# EtherCAT_Sheet.net
KiCad netlist of a schematic drawn in Altium Designer
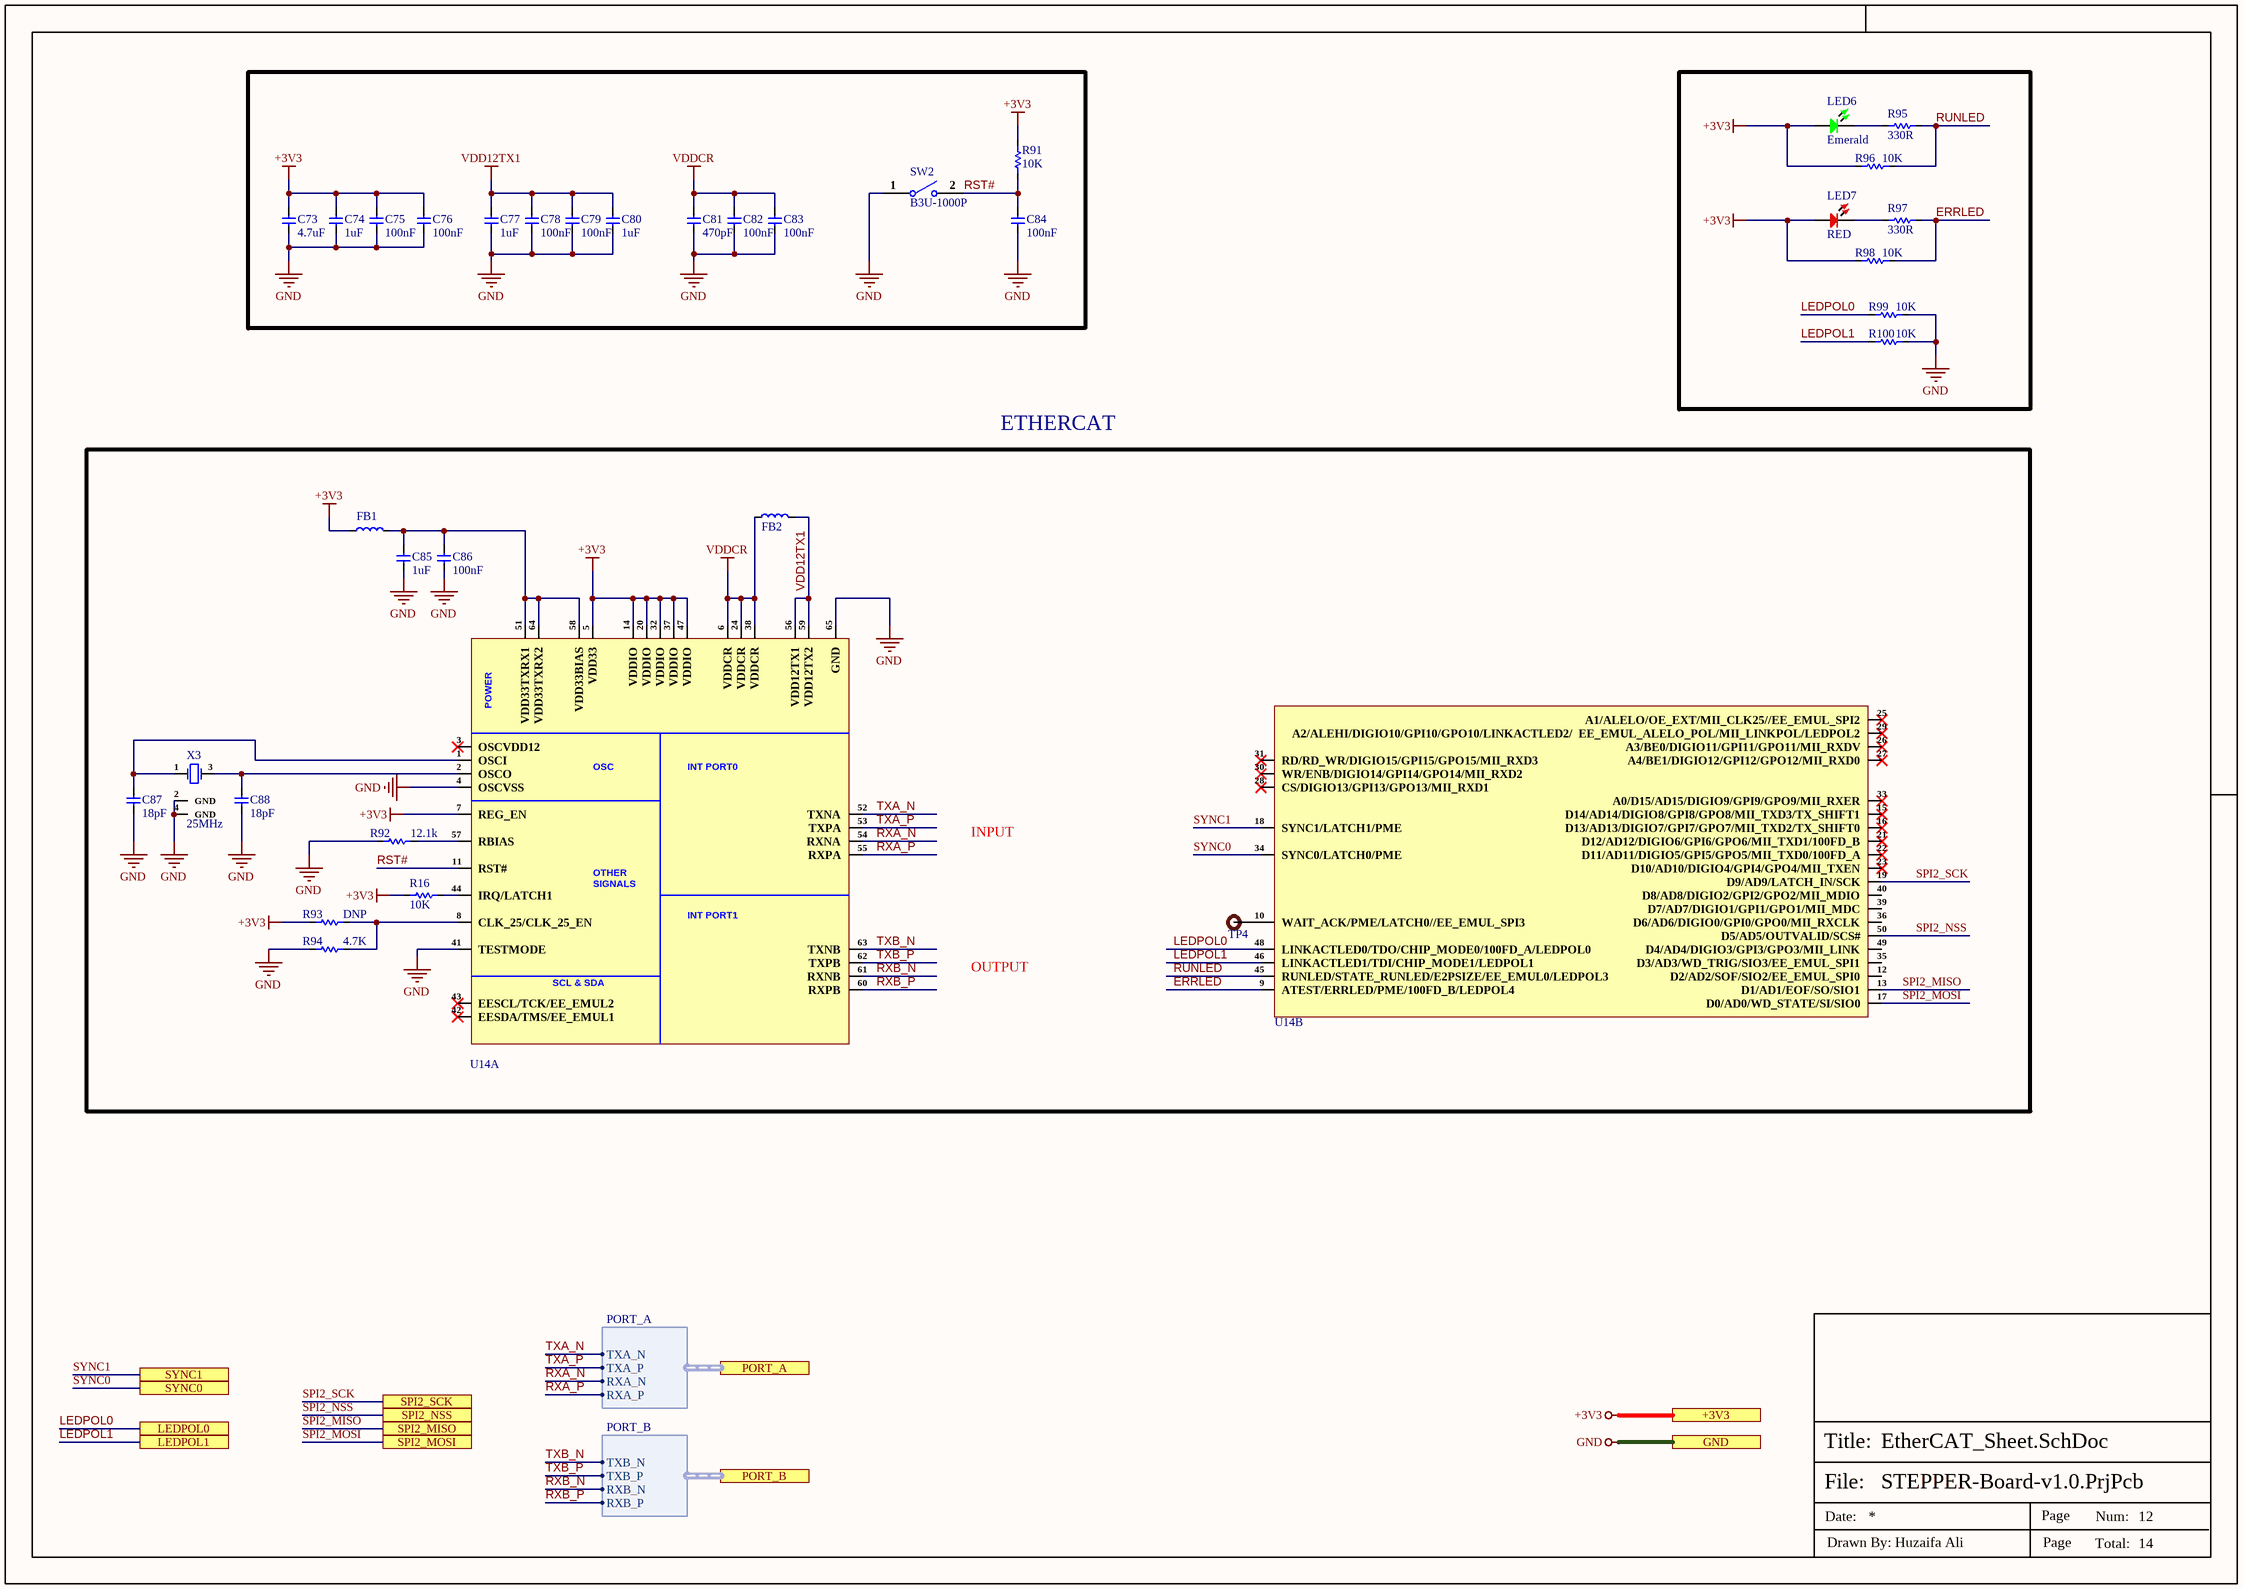
[diagram p0: EtherCAT_Sheet.SchDoc]

(export (version "E")
  (design (tool "Eeschema 10.0.6"))
  (components
    (comp (ref "C73")
      (value "4.7uF")
      (footprint "Cap-0402")
      (description "CAP CER 4.7UF 10V X5R 0402")
      (fields
        (field (name "MANUFACTURER") "Yageo")
        (field (name "MANUFACTURER PART NUMBER") "CC0402KRX5R6BB475")
      )
      (libsource (lib "eSpark Libraries") (part "CC0402KRX5R6BB475"))
    )
    (comp (ref "C74")
      (value "1uF")
      (footprint "Cap-0402")
      (description "CAP CER 1UF 10V X5R 0402")
      (fields
        (field (name "MANUFACTURER") "Yageo")
        (field (name "MANUFACTURER PART NUMBER") "CC0402KRX5R6BB105")
      )
      (libsource (lib "eSpark Libraries") (part "CC0402KRX5R6BB105"))
    )
    (comp (ref "C75")
      (value "100nF")
      (footprint "cap-0402")
      (description "CAP CER 0.1UF 50V X7R 0402")
      (fields
        (field (name "MANUFACTURER") "TDK")
        (field (name "MANUFACTURER PART NUMBER") "C1005X7R1H104KT000F")
      )
      (libsource (lib "eSpark Libraries") (part "C1005X7R1H104KT000F"))
    )
    (comp (ref "C76")
      (value "100nF")
      (footprint "cap-0402")
      (description "CAP CER 0.1UF 50V X7R 0402")
      (fields
        (field (name "MANUFACTURER") "TDK")
        (field (name "MANUFACTURER PART NUMBER") "C1005X7R1H104KT000F")
      )
      (libsource (lib "eSpark Libraries") (part "C1005X7R1H104KT000F"))
    )
    (comp (ref "C77")
      (value "1uF")
      (footprint "Cap-0402")
      (description "CAP CER 1UF 10V X5R 0402")
      (fields
        (field (name "MANUFACTURER") "Yageo")
        (field (name "MANUFACTURER PART NUMBER") "CC0402KRX5R6BB105")
      )
      (libsource (lib "eSpark Libraries") (part "CC0402KRX5R6BB105"))
    )
    (comp (ref "C78")
      (value "100nF")
      (footprint "cap-0402")
      (description "CAP CER 0.1UF 50V X7R 0402")
      (fields
        (field (name "MANUFACTURER") "TDK")
        (field (name "MANUFACTURER PART NUMBER") "C1005X7R1H104KT000F")
      )
      (libsource (lib "eSpark Libraries") (part "C1005X7R1H104KT000F"))
    )
    (comp (ref "C79")
      (value "100nF")
      (footprint "cap-0402")
      (description "CAP CER 0.1UF 50V X7R 0402")
      (fields
        (field (name "MANUFACTURER") "TDK")
        (field (name "MANUFACTURER PART NUMBER") "C1005X7R1H104KT000F")
      )
      (libsource (lib "eSpark Libraries") (part "C1005X7R1H104KT000F"))
    )
    (comp (ref "C80")
      (value "1uF")
      (footprint "Cap-0402")
      (description "CAP CER 1UF 10V X5R 0402")
      (fields
        (field (name "MANUFACTURER") "Yageo")
        (field (name "MANUFACTURER PART NUMBER") "CC0402KRX5R6BB105")
      )
      (libsource (lib "eSpark Libraries") (part "CC0402KRX5R6BB105"))
    )
    (comp (ref "C81")
      (value "470pF")
      (footprint "Cap-0603")
      (description "CAP CER 470PF 50V X7R 0603")
      (fields
        (field (name "MANUFACTURER") "Walsin Technologies")
        (field (name "MANUFACTURER PART NUMBER") "0603B471K500CT")
      )
      (libsource (lib "eSpark Libraries") (part "0603B471K500CT"))
    )
    (comp (ref "C82")
      (value "100nF")
      (footprint "cap-0402")
      (description "CAP CER 0.1UF 50V X7R 0402")
      (fields
        (field (name "MANUFACTURER") "TDK")
        (field (name "MANUFACTURER PART NUMBER") "C1005X7R1H104KT000F")
      )
      (libsource (lib "eSpark Libraries") (part "C1005X7R1H104KT000F"))
    )
    (comp (ref "C83")
      (value "100nF")
      (footprint "cap-0402")
      (description "CAP CER 0.1UF 50V X7R 0402")
      (fields
        (field (name "MANUFACTURER") "TDK")
        (field (name "MANUFACTURER PART NUMBER") "C1005X7R1H104KT000F")
      )
      (libsource (lib "eSpark Libraries") (part "C1005X7R1H104KT000F"))
    )
    (comp (ref "C84")
      (value "100nF")
      (footprint "cap-0402")
      (description "CAP CER 0.1UF 50V X7R 0402")
      (fields
        (field (name "MANUFACTURER") "TDK")
        (field (name "MANUFACTURER PART NUMBER") "C1005X7R1H104KT000F")
      )
      (libsource (lib "eSpark Libraries") (part "C1005X7R1H104KT000F"))
    )
    (comp (ref "C85")
      (value "1uF")
      (footprint "Cap-0402")
      (description "CAP CER 1UF 10V X5R 0402")
      (fields
        (field (name "MANUFACTURER") "Yageo")
        (field (name "MANUFACTURER PART NUMBER") "CC0402KRX5R6BB105")
      )
      (libsource (lib "eSpark Libraries") (part "CC0402KRX5R6BB105"))
    )
    (comp (ref "C86")
      (value "100nF")
      (footprint "cap-0402")
      (description "CAP CER 0.1UF 50V X7R 0402")
      (fields
        (field (name "MANUFACTURER") "TDK")
        (field (name "MANUFACTURER PART NUMBER") "C1005X7R1H104KT000F")
      )
      (libsource (lib "eSpark Libraries") (part "C1005X7R1H104KT000F"))
    )
    (comp (ref "C87")
      (value "18pF")
      (footprint "Cap-0402")
      (description "CAP CER 18PF 50V C0G/NP0 0402")
      (fields
        (field (name "MANUFACTURER") "Murata")
        (field (name "MANUFACTURER PART NUMBER") "GCM1555C1H180GA16D")
      )
      (libsource (lib "eSpark Libraries") (part "GCM1555C1H180GA16D"))
    )
    (comp (ref "C88")
      (value "18pF")
      (footprint "Cap-0402")
      (description "CAP CER 18PF 50V C0G/NP0 0402")
      (fields
        (field (name "MANUFACTURER") "Murata")
        (field (name "MANUFACTURER PART NUMBER") "GCM1555C1H180GA16D")
      )
      (libsource (lib "eSpark Libraries") (part "GCM1555C1H180GA16D"))
    )
    (comp (ref "FB1")
      (value "BLM15PG100SN1D")
      (footprint "IND-0402")
      (description "FERRITE BEAD 10 OHM 0402 1LN")
      (fields (field (name "MANUFACTURER") "Murata") (field (name "TOLERANCE") "25%"))
      (libsource (lib "eSpark Libraries") (part "BLM15PG100SN1D"))
    )
    (comp (ref "FB2")
      (value "BLM15PG100SN1D")
      (footprint "IND-0402")
      (description "FERRITE BEAD 10 OHM 0402 1LN")
      (fields (field (name "MANUFACTURER") "Murata") (field (name "TOLERANCE") "25%"))
      (libsource (lib "eSpark Libraries") (part "BLM15PG100SN1D"))
    )
    (comp (ref "LED6")
      (value "Emerald")
      (footprint "LED-0603")
      (description "Emerald 0603 Light Emitting Diodes (LED) ROHS")
      (fields
        (field (name "MANUFACTURER") "Foshan NationStar Optoelectronics")
        (field (name "MANUFACTURER PART NUMBER") "NCD0603G2")
      )
      (libsource (lib "eSpark Libraries") (part "NCD0603G2"))
    )
    (comp (ref "LED7")
      (value "RED")
      (footprint "LED-0603")
      (description "RED LED 0603 Light Emitting Diodes")
      (fields
        (field (name "MANUFACTURER") "Foshan NationStar Optoelectronics")
        (field (name "MANUFACTURER PART NUMBER") "NCD0603R3")
      )
      (libsource (lib "eSpark Libraries") (part "NCD0603R3"))
    )
    (comp (ref "R16")
      (value "10K")
      (footprint "Res-0402")
      (description "RES 10K OHM 1% 1/16W 0402")
      (fields
        (field (name "MANUFACTURER") "Yageo")
        (field (name "MANUFACTURER PART NUMBER") "RC0402FR-0710KL")
      )
      (libsource (lib "eSpark Libraries") (part "RC0402FR-0710KL"))
    )
    (comp (ref "R91")
      (value "10K")
      (footprint "Res-0402")
      (description "RES 10K OHM 1% 1/16W 0402")
      (fields
        (field (name "MANUFACTURER") "Yageo")
        (field (name "MANUFACTURER PART NUMBER") "RC0402FR-0710KL")
      )
      (libsource (lib "eSpark Libraries") (part "RC0402FR-0710KL"))
    )
    (comp (ref "R92")
      (value "12.1k")
      (footprint "Res-0402")
      (description "RES SMD 12.1KOHM 0.1% 1/16W 0402")
      (fields
        (field (name "MANUFACTURER") "Yageo")
        (field (name "MANUFACTURER PART NUMBER") "RT0402BRD0712K1L")
      )
      (libsource (lib "eSpark Libraries") (part "RT0402BRD0712K1L"))
    )
    (comp (ref "R93")
      (value "DNP")
      (footprint "Res-0402")
      (description "RES 4.7K OHM 1% 1/16W 0402")
      (fields
        (field (name "MANUFACTURER") "Yageo")
        (field (name "MANUFACTURER PART NUMBER") "RC0402FR-074K7L")
      )
      (libsource (lib "eSpark Libraries") (part "RC0402FR-074K7L"))
    )
    (comp (ref "R94")
      (value "4.7K")
      (footprint "Res-0402")
      (description "RES 4.7K OHM 1% 1/16W 0402")
      (fields
        (field (name "MANUFACTURER") "Yageo")
        (field (name "MANUFACTURER PART NUMBER") "RC0402FR-074K7L")
      )
      (libsource (lib "eSpark Libraries") (part "RC0402FR-074K7L"))
    )
    (comp (ref "R95")
      (value "330R")
      (footprint "Res-0603")
      (description "RES  SMD 330R 100 mW 0603")
      (fields
        (field (name "MANUFACTURER") "Yageo")
        (field (name "MANUFACTURER PART NUMBER") "RC0603JR-07330RL")
      )
      (libsource (lib "eSpark Libraries") (part "RC0603JR-07330RL"))
    )
    (comp (ref "R96")
      (value "10K")
      (footprint "Res-0402")
      (description "RES 10K OHM 1% 1/16W 0402")
      (fields
        (field (name "MANUFACTURER") "Yageo")
        (field (name "MANUFACTURER PART NUMBER") "RC0402FR-0710KL")
      )
      (libsource (lib "eSpark Libraries") (part "RC0402FR-0710KL"))
    )
    (comp (ref "R97")
      (value "330R")
      (footprint "Res-0603")
      (description "RES  SMD 330R 100 mW 0603")
      (fields
        (field (name "MANUFACTURER") "Yageo")
        (field (name "MANUFACTURER PART NUMBER") "RC0603JR-07330RL")
      )
      (libsource (lib "eSpark Libraries") (part "RC0603JR-07330RL"))
    )
    (comp (ref "R98")
      (value "10K")
      (footprint "Res-0402")
      (description "RES 10K OHM 1% 1/16W 0402")
      (fields
        (field (name "MANUFACTURER") "Yageo")
        (field (name "MANUFACTURER PART NUMBER") "RC0402FR-0710KL")
      )
      (libsource (lib "eSpark Libraries") (part "RC0402FR-0710KL"))
    )
    (comp (ref "R99")
      (value "10K")
      (footprint "Res-0402")
      (description "RES 10K OHM 1% 1/16W 0402")
      (fields
        (field (name "MANUFACTURER") "Yageo")
        (field (name "MANUFACTURER PART NUMBER") "RC0402FR-0710KL")
      )
      (libsource (lib "eSpark Libraries") (part "RC0402FR-0710KL"))
    )
    (comp (ref "R100")
      (value "10K")
      (footprint "Res-0402")
      (description "RES 10K OHM 1% 1/16W 0402")
      (fields
        (field (name "MANUFACTURER") "Yageo")
        (field (name "MANUFACTURER PART NUMBER") "RC0402FR-0710KL")
      )
      (libsource (lib "eSpark Libraries") (part "RC0402FR-0710KL"))
    )
    (comp (ref "SW2")
      (value "B3U-1000P")
      (footprint "B3U-1000P")
      (description "SWITCH TACTILE SPST-NO 0.05A 12V")
      (fields (field (name "MANUFACTURER") "Omron") (field (name "LCSC PART NUMBER") "C231329"))
      (libsource (lib "eSpark Libraries") (part "B3U-1000P"))
    )
    (comp (ref "TP4")
      (value "TEST POINT")
      (footprint "Test-point")
      (description "Test Point ON")
      (libsource (lib "eSpark Libraries") (part "TEST POINT"))
    )
    (comp (ref "U14")
      (value "LAN9253-SVB QFN64")
      (footprint "QFN-64-EP(9x9)")
      (description "2/3-PORT ETHERCAT SLAVE CTLR")
      (fields
        (field (name "MANUFACTURER") "Microchip")
        (field (name "MANUFACTURER PART NUMBER") "LAN9253-I/R4X")
      )
      (libsource (lib "eSpark Libraries") (part "LAN9253-SVB QFN64"))
    )
    (comp (ref "X3")
      (value "25MHz")
      (footprint "SMD3225-4P")
      (description "25MHz 贴片晶振 18pF ±10ppm ±20ppm SMD3225-4P Crystals ROHS")
      (fields (field (name "LCSC PART NUMBER") "C70593") (field (name "MANUFACTURER") "YXC"))
      (libsource (lib "eSpark Libraries") (part "X322525MRB4SI"))
    )
  )
  (nets
    (net (code "3") (name "+3V3") (class "Default")
      (node (ref "C73") (pin "2") (pinfunction "2_2") (pintype "passive"))
      (node (ref "C74") (pin "2") (pinfunction "2_2") (pintype "passive"))
      (node (ref "C75") (pin "2") (pinfunction "2_2") (pintype "passive"))
      (node (ref "C76") (pin "2") (pinfunction "2_2") (pintype "passive"))
      (node (ref "FB1") (pin "1") (pinfunction "1_1") (pintype "passive"))
      (node (ref "LED6") (pin "1") (pinfunction "1_1") (pintype "passive"))
      (node (ref "LED7") (pin "1") (pinfunction "1_1") (pintype "passive"))
      (node (ref "R16") (pin "1") (pinfunction "1_1") (pintype "passive"))
      (node (ref "R91") (pin "1") (pinfunction "1_1") (pintype "passive"))
      (node (ref "R93") (pin "1") (pinfunction "1_1") (pintype "passive"))
      (node (ref "R96") (pin "2") (pinfunction "2_2") (pintype "passive"))
      (node (ref "R98") (pin "2") (pinfunction "2_2") (pintype "passive"))
      (node (ref "U14") (pin "14") (pinfunction "VDDIO_14") (pintype "passive"))
      (node (ref "U14") (pin "20") (pinfunction "VDDIO_20") (pintype "passive"))
      (node (ref "U14") (pin "32") (pinfunction "VDDIO_32") (pintype "passive"))
      (node (ref "U14") (pin "37") (pinfunction "VDDIO_37") (pintype "passive"))
      (node (ref "U14") (pin "47") (pinfunction "VDDIO_47") (pintype "passive"))
      (node (ref "U14") (pin "5") (pinfunction "VDD33_5") (pintype "passive"))
      (node (ref "U14") (pin "7") (pinfunction "REG_EN_7") (pintype "passive"))
    )
    (net (code "4") (name "/ERRLED") (class "Default")
      (node (ref "R97") (pin "2") (pinfunction "2_2") (pintype "passive"))
      (node (ref "R98") (pin "1") (pinfunction "1_1") (pintype "passive"))
      (node (ref "U14") (pin "9") (pinfunction "ATEST/ERRLED/PME/100FD_B/LEDPOL4_9") (pintype "passive"))
    )
    (net (code "5") (name "/LEDPOL0") (class "Default")
      (node (ref "R99") (pin "2") (pinfunction "2_2") (pintype "passive"))
      (node (ref "U14") (pin "48") (pinfunction "LINKACTLED0/TDO/CHIP_MODE0/100FD_A/LEDPOL0_48") (pintype "passive"))
    )
    (net (code "6") (name "/LEDPOL1") (class "Default")
      (node (ref "R100") (pin "2") (pinfunction "2_2") (pintype "passive"))
      (node (ref "U14") (pin "46") (pinfunction "LINKACTLED1/TDI/CHIP_MODE1/LEDPOL1_46") (pintype "passive"))
    )
    (net (code "7") (name "/RST#") (class "Default")
      (node (ref "C84") (pin "2") (pinfunction "2_2") (pintype "passive"))
      (node (ref "R91") (pin "2") (pinfunction "2_2") (pintype "passive"))
      (node (ref "SW2") (pin "2") (pinfunction "2_2") (pintype "passive"))
      (node (ref "U14") (pin "11") (pinfunction "RST#_11") (pintype "passive"))
    )
    (net (code "8") (name "/RUNLED") (class "Default")
      (node (ref "R95") (pin "2") (pinfunction "2_2") (pintype "passive"))
      (node (ref "R96") (pin "1") (pinfunction "1_1") (pintype "passive"))
      (node (ref "U14") (pin "45") (pinfunction "RUNLED/STATE_RUNLED/E2PSIZE/EE_EMUL0/LEDPOL3_45") (pintype "passive"))
    )
    (net (code "9") (name "/RXA_N") (class "Default")
      (node (ref "U14") (pin "54") (pinfunction "RXNA_54") (pintype "passive"))
    )
    (net (code "10") (name "/RXA_P") (class "Default")
      (node (ref "U14") (pin "55") (pinfunction "RXPA_55") (pintype "passive"))
    )
    (net (code "11") (name "/RXB_N") (class "Default")
      (node (ref "U14") (pin "61") (pinfunction "RXNB_61") (pintype "passive"))
    )
    (net (code "12") (name "/RXB_P") (class "Default")
      (node (ref "U14") (pin "60") (pinfunction "RXPB_60") (pintype "passive"))
    )
    (net (code "13") (name "/SPI2_MISO") (class "Default")
      (node (ref "U14") (pin "13") (pinfunction "D1/AD1/EOF/SO/SIO1_13") (pintype "passive"))
    )
    (net (code "14") (name "/SPI2_MOSI") (class "Default")
      (node (ref "U14") (pin "17") (pinfunction "D0/AD0/WD_STATE/SI/SIO0_17") (pintype "passive"))
    )
    (net (code "15") (name "/SPI2_NSS") (class "Default")
      (node (ref "U14") (pin "50") (pinfunction "D5/AD5/OUTVALID/SCS#_50") (pintype "passive"))
    )
    (net (code "16") (name "/SPI2_SCK") (class "Default")
      (node (ref "U14") (pin "19") (pinfunction "D9/AD9/LATCH_IN/SCK_19") (pintype "passive"))
    )
    (net (code "17") (name "/SYNC0") (class "Default")
      (node (ref "U14") (pin "34") (pinfunction "SYNC0/LATCH0/PME_34") (pintype "passive"))
    )
    (net (code "18") (name "/SYNC1") (class "Default")
      (node (ref "U14") (pin "18") (pinfunction "SYNC1/LATCH1/PME_18") (pintype "passive"))
    )
    (net (code "19") (name "/TXA_N") (class "Default")
      (node (ref "U14") (pin "52") (pinfunction "TXNA_52") (pintype "passive"))
    )
    (net (code "20") (name "/TXA_P") (class "Default")
      (node (ref "U14") (pin "53") (pinfunction "TXPA_53") (pintype "passive"))
    )
    (net (code "21") (name "/TXB_N") (class "Default")
      (node (ref "U14") (pin "63") (pinfunction "TXNB_63") (pintype "passive"))
    )
    (net (code "22") (name "/TXB_P") (class "Default")
      (node (ref "U14") (pin "62") (pinfunction "TXPB_62") (pintype "passive"))
    )
    (net (code "25") (name "GND") (class "Default")
      (node (ref "C73") (pin "1") (pinfunction "1_1") (pintype "passive"))
      (node (ref "C74") (pin "1") (pinfunction "1_1") (pintype "passive"))
      (node (ref "C75") (pin "1") (pinfunction "1_1") (pintype "passive"))
      (node (ref "C76") (pin "1") (pinfunction "1_1") (pintype "passive"))
      (node (ref "C77") (pin "1") (pinfunction "1_1") (pintype "passive"))
      (node (ref "C78") (pin "1") (pinfunction "1_1") (pintype "passive"))
      (node (ref "C79") (pin "1") (pinfunction "1_1") (pintype "passive"))
      (node (ref "C80") (pin "1") (pinfunction "1_1") (pintype "passive"))
      (node (ref "C81") (pin "1") (pinfunction "1_1") (pintype "passive"))
      (node (ref "C82") (pin "1") (pinfunction "1_1") (pintype "passive"))
      (node (ref "C83") (pin "1") (pinfunction "1_1") (pintype "passive"))
      (node (ref "C84") (pin "1") (pinfunction "1_1") (pintype "passive"))
      (node (ref "C85") (pin "1") (pinfunction "1_1") (pintype "passive"))
      (node (ref "C86") (pin "1") (pinfunction "1_1") (pintype "passive"))
      (node (ref "C87") (pin "2") (pinfunction "2_2") (pintype "passive"))
      (node (ref "C88") (pin "2") (pinfunction "2_2") (pintype "passive"))
      (node (ref "R100") (pin "1") (pinfunction "1_1") (pintype "passive"))
      (node (ref "R92") (pin "1") (pinfunction "1_1") (pintype "passive"))
      (node (ref "R94") (pin "1") (pinfunction "1_1") (pintype "passive"))
      (node (ref "R99") (pin "1") (pinfunction "1_1") (pintype "passive"))
      (node (ref "SW2") (pin "1") (pinfunction "1_1") (pintype "passive"))
      (node (ref "U14") (pin "4") (pinfunction "OSCVSS_4") (pintype "passive"))
      (node (ref "U14") (pin "41") (pinfunction "TESTMODE_41") (pintype "passive"))
      (node (ref "U14") (pin "65") (pinfunction "GND_65") (pintype "passive"))
      (node (ref "X3") (pin "2") (pinfunction "GND_2") (pintype "passive"))
      (node (ref "X3") (pin "4") (pinfunction "GND_4") (pintype "passive"))
    )
    (net (code "26") (name "Net-(LED6-Pad2)") (class "Default")
      (node (ref "LED6") (pin "2") (pinfunction "2_2") (pintype "passive"))
      (node (ref "R95") (pin "1") (pinfunction "1_1") (pintype "passive"))
    )
    (net (code "27") (name "Net-(LED7-Pad2)") (class "Default")
      (node (ref "LED7") (pin "2") (pinfunction "2_2") (pintype "passive"))
      (node (ref "R97") (pin "1") (pinfunction "1_1") (pintype "passive"))
    )
    (net (code "28") (name "Net-(U14A-CLK_25{slash}CLK_25_EN)") (class "Default")
      (node (ref "R93") (pin "2") (pinfunction "2_2") (pintype "passive"))
      (node (ref "R94") (pin "2") (pinfunction "2_2") (pintype "passive"))
      (node (ref "U14") (pin "8") (pinfunction "CLK_25/CLK_25_EN_8") (pintype "passive"))
    )
    (net (code "29") (name "Net-(U14A-IRQ{slash}LATCH1)") (class "Default")
      (node (ref "R16") (pin "2") (pinfunction "2_2") (pintype "passive"))
      (node (ref "U14") (pin "44") (pinfunction "IRQ/LATCH1_44") (pintype "passive"))
    )
    (net (code "30") (name "Net-(U14A-OSCI)") (class "Default")
      (node (ref "C87") (pin "1") (pinfunction "1_1") (pintype "passive"))
      (node (ref "U14") (pin "1") (pinfunction "OSCI_1") (pintype "passive"))
      (node (ref "X3") (pin "1") (pinfunction "CRYSTAL_1") (pintype "passive"))
    )
    (net (code "31") (name "Net-(U14A-OSCO)") (class "Default")
      (node (ref "C88") (pin "1") (pinfunction "1_1") (pintype "passive"))
      (node (ref "U14") (pin "2") (pinfunction "OSCO_2") (pintype "passive"))
      (node (ref "X3") (pin "3") (pinfunction "CRYSTAL_3") (pintype "passive"))
    )
    (net (code "32") (name "Net-(U14A-RBIAS)") (class "Default")
      (node (ref "R92") (pin "2") (pinfunction "2_2") (pintype "passive"))
      (node (ref "U14") (pin "57") (pinfunction "RBIAS_57") (pintype "passive"))
    )
    (net (code "33") (name "Net-(U14A-VDD33BIAS)") (class "Default")
      (node (ref "C85") (pin "2") (pinfunction "2_2") (pintype "passive"))
      (node (ref "C86") (pin "2") (pinfunction "2_2") (pintype "passive"))
      (node (ref "FB1") (pin "2") (pinfunction "2_2") (pintype "passive"))
      (node (ref "U14") (pin "51") (pinfunction "VDD33TXRX1_51") (pintype "passive"))
      (node (ref "U14") (pin "58") (pinfunction "VDD33BIAS_58") (pintype "passive"))
      (node (ref "U14") (pin "64") (pinfunction "VDD33TXRX2_64") (pintype "passive"))
    )
    (net (code "34") (name "Net-(U14B-WAIT_ACK{slash}PME{slash}LATCH0{slash}{slash}EE_EMUL_SPI3)") (class "Default")
      (node (ref "TP4") (pin "1") (pinfunction "1_1") (pintype "passive"))
      (node (ref "U14") (pin "10") (pinfunction "WAIT_ACK/PME/LATCH0//EE_EMUL_SPI3_10") (pintype "passive"))
    )
    (net (code "35") (name "VDD12TX1") (class "Default")
      (node (ref "C77") (pin "2") (pinfunction "2_2") (pintype "passive"))
      (node (ref "C78") (pin "2") (pinfunction "2_2") (pintype "passive"))
      (node (ref "C79") (pin "2") (pinfunction "2_2") (pintype "passive"))
      (node (ref "C80") (pin "2") (pinfunction "2_2") (pintype "passive"))
      (node (ref "FB2") (pin "2") (pinfunction "2_2") (pintype "passive"))
      (node (ref "U14") (pin "56") (pinfunction "VDD12TX1_56") (pintype "passive"))
      (node (ref "U14") (pin "59") (pinfunction "VDD12TX2_59") (pintype "passive"))
    )
    (net (code "36") (name "VDDCR") (class "Default")
      (node (ref "C81") (pin "2") (pinfunction "2_2") (pintype "passive"))
      (node (ref "C82") (pin "2") (pinfunction "2_2") (pintype "passive"))
      (node (ref "C83") (pin "2") (pinfunction "2_2") (pintype "passive"))
      (node (ref "FB2") (pin "1") (pinfunction "1_1") (pintype "passive"))
      (node (ref "U14") (pin "24") (pinfunction "VDDCR_24") (pintype "passive"))
      (node (ref "U14") (pin "38") (pinfunction "VDDCR_38") (pintype "passive"))
      (node (ref "U14") (pin "6") (pinfunction "VDDCR_6") (pintype "passive"))
    )
    (net (code "37") (name "unconnected-(U14A-EESCL{slash}TCK{slash}EE_EMUL2-Pad43)") (class "Default")
      (node (ref "U14") (pin "43") (pinfunction "EESCL/TCK/EE_EMUL2_43") (pintype "passive+no_connect"))
    )
    (net (code "38") (name "unconnected-(U14A-EESDA{slash}TMS{slash}EE_EMUL1-Pad42)") (class "Default")
      (node (ref "U14") (pin "42") (pinfunction "EESDA/TMS/EE_EMUL1_42") (pintype "passive+no_connect"))
    )
    (net (code "39") (name "unconnected-(U14A-OSCVDD12-Pad3)") (class "Default")
      (node (ref "U14") (pin "3") (pinfunction "OSCVDD12_3") (pintype "passive+no_connect"))
    )
    (net (code "40") (name "unconnected-(U14B-A0{slash}D15{slash}AD15{slash}DIGIO9{slash}GPI9{slash}GPO9{slash}MII_RXER-Pad33)") (class "Default")
      (node (ref "U14") (pin "33") (pinfunction "A0/D15/AD15/DIGIO9/GPI9/GPO9/MII_RXER_33") (pintype "passive+no_connect"))
    )
    (net (code "41") (name "unconnected-(U14B-A1{slash}ALELO{slash}OE_EXT{slash}MII_CLK25{slash}{slash}EE_EMUL_SPI2-Pad25)") (class "Default")
      (node (ref "U14") (pin "25") (pinfunction "A1/ALELO/OE_EXT/MII_CLK25//EE_EMUL_SPI2_25") (pintype "passive+no_connect"))
    )
    (net (code "42") (name "unconnected-(U14B-A2{slash}ALEHI{slash}DIGIO10{slash}GPI10{slash}GPO10{slash}LINKACTLED2{slash}__EE_EMUL_ALELO_POL{slash}MII_LINKPOL{slash}LEDPOL2-Pad29)") (class "Default")
      (node (ref "U14") (pin "29") (pinfunction "A2/ALEHI/DIGIO10/GPI10/GPO10/LINKACTLED2/__EE_EMUL_ALELO_POL/MII_LINKPOL/LEDPOL2_29") (pintype "passive+no_connect"))
    )
    (net (code "43") (name "unconnected-(U14B-A3{slash}BE0{slash}DIGIO11{slash}GPI11{slash}GPO11{slash}MII_RXDV-Pad26)") (class "Default")
      (node (ref "U14") (pin "26") (pinfunction "A3/BE0/DIGIO11/GPI11/GPO11/MII_RXDV_26") (pintype "passive+no_connect"))
    )
    (net (code "44") (name "unconnected-(U14B-A4{slash}BE1{slash}DIGIO12{slash}GPI12{slash}GPO12{slash}MII_RXD0-Pad27)") (class "Default")
      (node (ref "U14") (pin "27") (pinfunction "A4/BE1/DIGIO12/GPI12/GPO12/MII_RXD0_27") (pintype "passive+no_connect"))
    )
    (net (code "45") (name "unconnected-(U14B-CS{slash}DIGIO13{slash}GPI13{slash}GPO13{slash}MII_RXD1-Pad28)") (class "Default")
      (node (ref "U14") (pin "28") (pinfunction "CS/DIGIO13/GPI13/GPO13/MII_RXD1_28") (pintype "passive+no_connect"))
    )
    (net (code "46") (name "unconnected-(U14B-D2{slash}AD2{slash}SOF{slash}SIO2{slash}EE_EMUL_SPI0-Pad12)") (class "Default")
      (node (ref "U14") (pin "12") (pinfunction "D2/AD2/SOF/SIO2/EE_EMUL_SPI0_12") (pintype "passive"))
    )
    (net (code "47") (name "unconnected-(U14B-D3{slash}AD3{slash}WD_TRIG{slash}SIO3{slash}EE_EMUL_SPI1-Pad35)") (class "Default")
      (node (ref "U14") (pin "35") (pinfunction "D3/AD3/WD_TRIG/SIO3/EE_EMUL_SPI1_35") (pintype "passive"))
    )
    (net (code "48") (name "unconnected-(U14B-D4{slash}AD4{slash}DIGIO3{slash}GPI3{slash}GPO3{slash}MII_LINK-Pad49)") (class "Default")
      (node (ref "U14") (pin "49") (pinfunction "D4/AD4/DIGIO3/GPI3/GPO3/MII_LINK_49") (pintype "passive"))
    )
    (net (code "49") (name "unconnected-(U14B-D6{slash}AD6{slash}DIGIO0{slash}GPI0{slash}GPO0{slash}MII_RXCLK-Pad36)") (class "Default")
      (node (ref "U14") (pin "36") (pinfunction "D6/AD6/DIGIO0/GPI0/GPO0/MII_RXCLK_36") (pintype "passive"))
    )
    (net (code "50") (name "unconnected-(U14B-D7{slash}AD7{slash}DIGIO1{slash}GPI1{slash}GPO1{slash}MII_MDC-Pad39)") (class "Default")
      (node (ref "U14") (pin "39") (pinfunction "D7/AD7/DIGIO1/GPI1/GPO1/MII_MDC_39") (pintype "passive"))
    )
    (net (code "51") (name "unconnected-(U14B-D8{slash}AD8{slash}DIGIO2{slash}GPI2{slash}GPO2{slash}MII_MDIO-Pad40)") (class "Default")
      (node (ref "U14") (pin "40") (pinfunction "D8/AD8/DIGIO2/GPI2/GPO2/MII_MDIO_40") (pintype "passive"))
    )
    (net (code "52") (name "unconnected-(U14B-D10{slash}AD10{slash}DIGIO4{slash}GPI4{slash}GPO4{slash}MII_TXEN-Pad23)") (class "Default")
      (node (ref "U14") (pin "23") (pinfunction "D10/AD10/DIGIO4/GPI4/GPO4/MII_TXEN_23") (pintype "passive+no_connect"))
    )
    (net (code "53") (name "unconnected-(U14B-D11{slash}AD11{slash}DIGIO5{slash}GPI5{slash}GPO5{slash}MII_TXD0{slash}100FD_A-Pad22)") (class "Default")
      (node (ref "U14") (pin "22") (pinfunction "D11/AD11/DIGIO5/GPI5/GPO5/MII_TXD0/100FD_A_22") (pintype "passive+no_connect"))
    )
    (net (code "54") (name "unconnected-(U14B-D12{slash}AD12{slash}DIGIO6{slash}GPI6{slash}GPO6{slash}MII_TXD1{slash}100FD_B-Pad21)") (class "Default")
      (node (ref "U14") (pin "21") (pinfunction "D12/AD12/DIGIO6/GPI6/GPO6/MII_TXD1/100FD_B_21") (pintype "passive+no_connect"))
    )
    (net (code "55") (name "unconnected-(U14B-D13{slash}AD13{slash}DIGIO7{slash}GPI7{slash}GPO7{slash}MII_TXD2{slash}TX_SHIFT0-Pad16)") (class "Default")
      (node (ref "U14") (pin "16") (pinfunction "D13/AD13/DIGIO7/GPI7/GPO7/MII_TXD2/TX_SHIFT0_16") (pintype "passive+no_connect"))
    )
    (net (code "56") (name "unconnected-(U14B-D14{slash}AD14{slash}DIGIO8{slash}GPI8{slash}GPO8{slash}MII_TXD3{slash}TX_SHIFT1-Pad15)") (class "Default")
      (node (ref "U14") (pin "15") (pinfunction "D14/AD14/DIGIO8/GPI8/GPO8/MII_TXD3/TX_SHIFT1_15") (pintype "passive+no_connect"))
    )
    (net (code "57") (name "unconnected-(U14B-RD{slash}RD_WR{slash}DIGIO15{slash}GPI15{slash}GPO15{slash}MII_RXD3-Pad31)") (class "Default")
      (node (ref "U14") (pin "31") (pinfunction "RD/RD_WR/DIGIO15/GPI15/GPO15/MII_RXD3_31") (pintype "passive+no_connect"))
    )
    (net (code "58") (name "unconnected-(U14B-WR{slash}ENB{slash}DIGIO14{slash}GPI14{slash}GPO14{slash}MII_RXD2-Pad30)") (class "Default")
      (node (ref "U14") (pin "30") (pinfunction "WR/ENB/DIGIO14/GPI14/GPO14/MII_RXD2_30") (pintype "passive+no_connect"))
    )
  )
)
